# USBStereoAudioCodec.net
KiCad netlist of a schematic drawn in Altium Designer
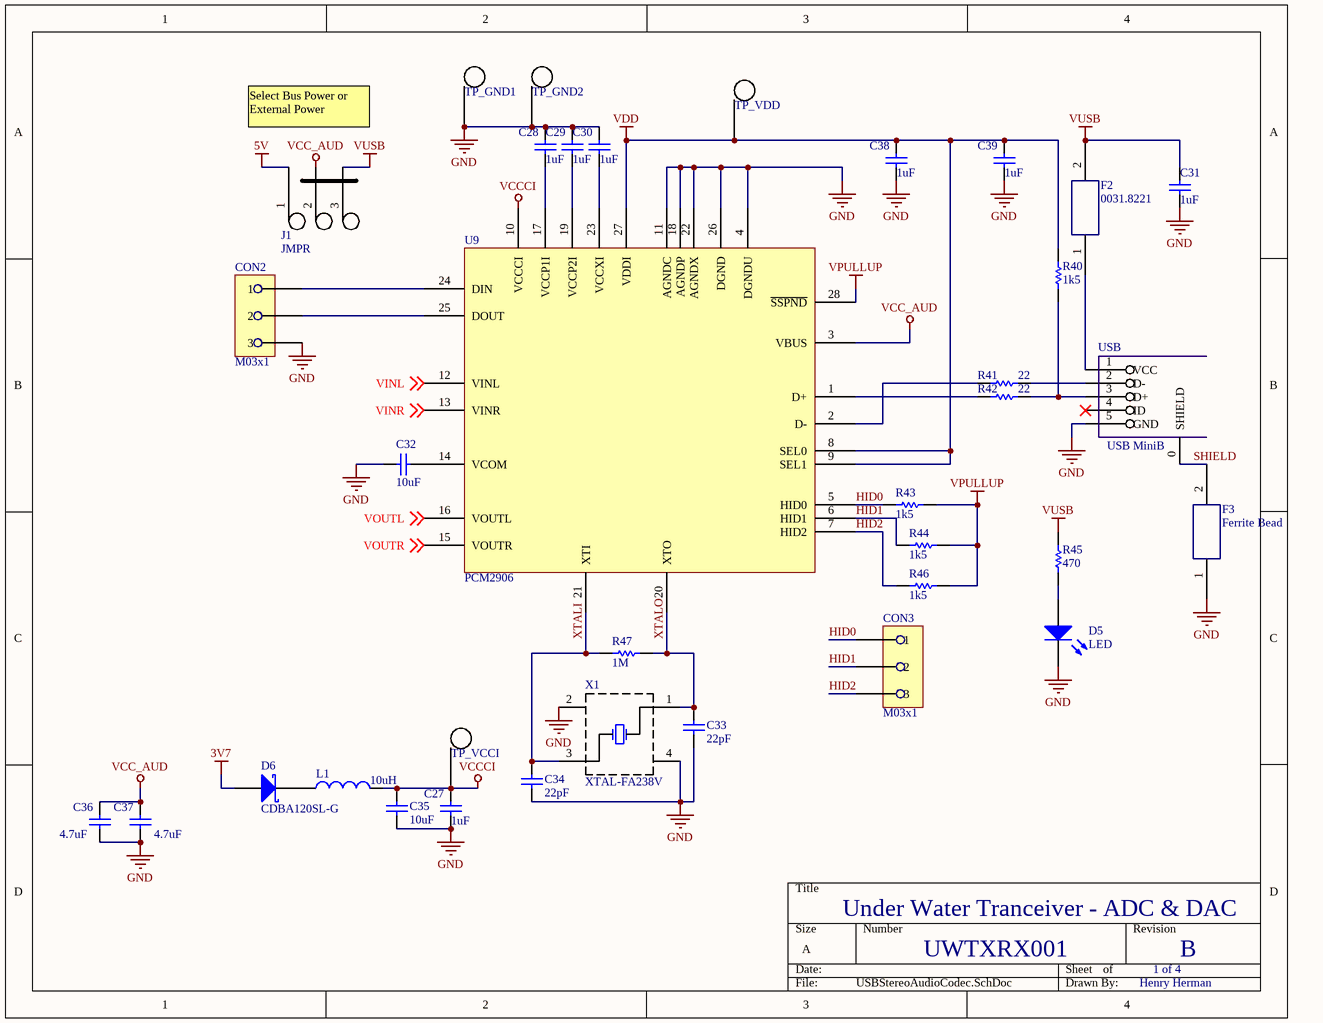
[diagram p0: USBStereoAudioCodec.SchDoc]

(export (version "E")
  (design (tool "Eeschema 10.0.6"))
  (components
    (comp (ref "C27")
      (value "1uF")
      (footprint "SM/C_0805")
      (description "CAP")
      (libsource (lib "Henry1_20_2010") (part "CAP"))
    )
    (comp (ref "C28")
      (value "1uF")
      (footprint "SM/C_0805")
      (description "CAP")
      (libsource (lib "Henry1_20_2010") (part "CAP"))
    )
    (comp (ref "C29")
      (value "1uF")
      (footprint "SM/C_0805")
      (description "CAP")
      (libsource (lib "Henry1_20_2010") (part "CAP"))
    )
    (comp (ref "C30")
      (value "1uF")
      (footprint "SM/C_0805")
      (description "CAP")
      (libsource (lib "Henry1_20_2010") (part "CAP"))
    )
    (comp (ref "C31")
      (value "1uF")
      (footprint "SM/C_0805")
      (description "CAP")
      (libsource (lib "Henry1_20_2010") (part "CAP"))
    )
    (comp (ref "C32")
      (value "10uF")
      (footprint "SM/C_0805")
      (description "CAP")
      (libsource (lib "Henry1_20_2010") (part "CAP"))
    )
    (comp (ref "C33")
      (value "22pF")
      (footprint "SM/C_0805")
      (description "CAP")
      (libsource (lib "Henry1_20_2010") (part "CAP"))
    )
    (comp (ref "C34")
      (value "22pF")
      (footprint "SM/C_0805")
      (description "CAP")
      (libsource (lib "Henry1_20_2010") (part "CAP"))
    )
    (comp (ref "C35")
      (value "10uF")
      (footprint "SM/C_0805")
      (description "CAP")
      (libsource (lib "Henry1_20_2010") (part "CAP"))
    )
    (comp (ref "C36")
      (value "4.7uF")
      (footprint "SM/C_0805")
      (description "CAP")
      (libsource (lib "Henry1_20_2010") (part "CAP"))
    )
    (comp (ref "C37")
      (value "CAP")
      (footprint "SM/C_0805")
      (fields (field (name "LABEL") "4.7uF"))
      (libsource (lib "Henry1_20_2010") (part "CAP"))
    )
    (comp (ref "C38")
      (value "1uF")
      (footprint "SM/C_0805")
      (description "CAP")
      (libsource (lib "Henry1_20_2010") (part "CAP"))
    )
    (comp (ref "C39")
      (value "1uF")
      (footprint "SM/C_0805")
      (description "CAP")
      (libsource (lib "Henry1_20_2010") (part "CAP"))
    )
    (comp (ref "CON2") (value "M03x1") (footprint "M03x1") (libsource (lib "Henry1_20_2010") (part "M03x1")))
    (comp (ref "CON3") (value "M03x1") (footprint "M03x1") (libsource (lib "") (part "M03x1_1")))
    (comp (ref "D5") (value "LED") (footprint "LED-0805") (libsource (lib "Henry1_20_2010") (part "LED")))
    (comp (ref "D6")
      (value "CDBA120SL-G")
      (footprint "D0-214AC")
      (libsource (lib "Henry1_20_2010") (part "Schottky Diode_AC"))
    )
    (comp (ref "F2")
      (value "0031.8221")
      (footprint "SM/R_0805")
      (description "Ferrite Bead")
      (fields (field (name "PUBLISHER") "Altium Limited"))
      (libsource (lib "Henry1_20_2010") (part "Ferrite Bead"))
    )
    (comp (ref "F3")
      (value "Ferrite Bead")
      (footprint "SM/R_0805")
      (fields (field (name "PUBLISHER") "Altium Limited"))
      (libsource (lib "Henry1_20_2010") (part "Ferrite Bead"))
    )
    (comp (ref "J1")
      (value "JMPR")
      (footprint "M03x1-nolock")
      (description "Jumper")
      (fields (field (name "PUBLISHER") "Altium Limited"))
      (libsource (lib "Henry1_20_2010") (part "JMPR-3"))
    )
    (comp (ref "L1")
      (value "10uH")
      (footprint "SM/L_0805")
      (fields (field (name "Comment") "Inductor"))
      (libsource (lib "Henry1_20_2010") (part "Inductor"))
    )
    (comp (ref "R40")
      (value "1k5")
      (footprint "SM/R_0805")
      (description "Resistor")
      (fields (field (name "Comment") "Res") (field (name "PUBLISHER") "Altium Limited"))
      (libsource (lib "Henry1_20_2010") (part "Res"))
    )
    (comp (ref "R41")
      (value "22")
      (footprint "SM/R_0805")
      (description "Resistor")
      (fields (field (name "Comment") "Res") (field (name "PUBLISHER") "Altium Limited"))
      (libsource (lib "Henry1_20_2010") (part "Res"))
    )
    (comp (ref "R42")
      (value "22")
      (footprint "SM/R_0805")
      (description "Resistor")
      (fields (field (name "Comment") "Res") (field (name "PUBLISHER") "Altium Limited"))
      (libsource (lib "Henry1_20_2010") (part "Res"))
    )
    (comp (ref "R43")
      (value "1k5")
      (footprint "SM/R_0805")
      (description "Resistor")
      (fields (field (name "Comment") "Res") (field (name "PUBLISHER") "Altium Limited"))
      (libsource (lib "Henry1_20_2010") (part "Res"))
    )
    (comp (ref "R44")
      (value "1k5")
      (footprint "SM/R_0805")
      (description "Resistor")
      (fields (field (name "Comment") "Res") (field (name "PUBLISHER") "Altium Limited"))
      (libsource (lib "Henry1_20_2010") (part "Res"))
    )
    (comp (ref "R45")
      (value "470")
      (footprint "SM/R_0805")
      (description "Resistor")
      (fields (field (name "Comment") "Res") (field (name "PUBLISHER") "Altium Limited"))
      (libsource (lib "Henry1_20_2010") (part "Res"))
    )
    (comp (ref "R46")
      (value "1k5")
      (footprint "SM/R_0805")
      (description "Resistor")
      (fields (field (name "Comment") "Res") (field (name "PUBLISHER") "Altium Limited"))
      (libsource (lib "Henry1_20_2010") (part "Res"))
    )
    (comp (ref "R47")
      (value "1M")
      (footprint "SM/R_0805")
      (description "Resistor")
      (fields (field (name "Comment") "Res") (field (name "PUBLISHER") "Altium Limited"))
      (libsource (lib "Henry1_20_2010") (part "Res"))
    )
    (comp (ref "TP_GND1")
      (value "TEST_PT")
      (footprint "TEST_PT_SMD")
      (libsource (lib "Henry1_20_2010") (part "TEST_PT"))
    )
    (comp (ref "TP_GND2")
      (value "TEST_PT")
      (footprint "TEST_PT_SMD")
      (libsource (lib "Henry1_20_2010") (part "TEST_PT"))
    )
    (comp (ref "TP_VCCI")
      (value "TEST_PT")
      (footprint "TEST_PT_SMD")
      (libsource (lib "Henry1_20_2010") (part "TEST_PT"))
    )
    (comp (ref "TP_VDD")
      (value "TEST_PT")
      (footprint "TEST_PT_SMD")
      (libsource (lib "Henry1_20_2010") (part "TEST_PT"))
    )
    (comp (ref "U9")
      (value "PCM2906")
      (footprint "SSOP-28PIN-TI")
      (libsource (lib "Henry1_20_2010") (part "PCM2906C"))
    )
    (comp (ref "USB")
      (value "USB MiniB")
      (footprint "USB-MINIB")
      (description "Mini USB")
      (fields (field (name "PUBLISHER") "Altium Limited"))
      (libsource (lib "Henry1_20_2010") (part "USB MiniB"))
    )
    (comp (ref "X1")
      (value "XTAL-FA238V")
      (footprint "XTAL 12MHz SMD")
      (libsource (lib "Henry1_20_2010") (part "XTAL-FA238V"))
    )
  )
  (nets
    (net (code "1") (name "/HID0") (class "Default")
      (node (ref "CON3") (pin "1") (pinfunction "1_1") (pintype "passive"))
      (node (ref "R43") (pin "1") (pinfunction "1_1") (pintype "passive"))
      (node (ref "U9") (pin "5") (pinfunction "HID0_5") (pintype "passive"))
    )
    (net (code "2") (name "/HID1") (class "Default")
      (node (ref "CON3") (pin "2") (pinfunction "2_2") (pintype "passive"))
      (node (ref "R44") (pin "1") (pinfunction "1_1") (pintype "passive"))
      (node (ref "U9") (pin "6") (pinfunction "HID1_6") (pintype "passive"))
    )
    (net (code "3") (name "/HID2") (class "Default")
      (node (ref "CON3") (pin "3") (pinfunction "3_3") (pintype "passive"))
      (node (ref "R46") (pin "1") (pinfunction "1_1") (pintype "passive"))
      (node (ref "U9") (pin "7") (pinfunction "HID2_7") (pintype "passive"))
    )
    (net (code "4") (name "/SHIELD") (class "Default")
      (node (ref "F3") (pin "2") (pintype "power_in"))
      (node (ref "USB") (pin "0") (pinfunction "SHIELD_0") (pintype "power_in"))
    )
    (net (code "5") (name "/XTALI") (class "Default")
      (node (ref "C34") (pin "2") (pinfunction "2_2") (pintype "passive"))
      (node (ref "R47") (pin "2") (pinfunction "2_2") (pintype "passive"))
      (node (ref "U9") (pin "21") (pinfunction "XTI_21") (pintype "passive"))
      (node (ref "X1") (pin "3") (pinfunction "3_3") (pintype "passive"))
    )
    (net (code "6") (name "/XTALO") (class "Default")
      (node (ref "C33") (pin "2") (pinfunction "2_2") (pintype "passive"))
      (node (ref "R47") (pin "1") (pinfunction "1_1") (pintype "passive"))
      (node (ref "U9") (pin "20") (pinfunction "XTO_20") (pintype "passive"))
      (node (ref "X1") (pin "1") (pinfunction "1_1") (pintype "passive"))
    )
    (net (code "7") (name "3V7") (class "Default")
      (node (ref "D6") (pin "A") (pinfunction "A_A") (pintype "passive"))
    )
    (net (code "8") (name "5V") (class "Default")
      (node (ref "J1") (pin "1") (pinfunction "P1_1") (pintype "power_in"))
    )
    (net (code "9") (name "GND") (class "Default")
      (node (ref "C27") (pin "2") (pinfunction "2_2") (pintype "passive"))
      (node (ref "C28") (pin "1") (pinfunction "1_1") (pintype "passive"))
      (node (ref "C29") (pin "1") (pinfunction "1_1") (pintype "passive"))
      (node (ref "C30") (pin "1") (pinfunction "1_1") (pintype "passive"))
      (node (ref "C31") (pin "2") (pinfunction "2_2") (pintype "passive"))
      (node (ref "C32") (pin "2") (pinfunction "2_2") (pintype "passive"))
      (node (ref "C33") (pin "1") (pinfunction "1_1") (pintype "passive"))
      (node (ref "C34") (pin "1") (pinfunction "1_1") (pintype "passive"))
      (node (ref "C35") (pin "1") (pinfunction "1_1") (pintype "passive"))
      (node (ref "C36") (pin "2") (pinfunction "2_2") (pintype "passive"))
      (node (ref "C37") (pin "2") (pinfunction "2_2") (pintype "passive"))
      (node (ref "C38") (pin "2") (pinfunction "2_2") (pintype "passive"))
      (node (ref "C39") (pin "2") (pinfunction "2_2") (pintype "passive"))
      (node (ref "CON2") (pin "3") (pinfunction "3_3") (pintype "passive"))
      (node (ref "D5") (pin "2") (pinfunction "K_2") (pintype "passive"))
      (node (ref "F3") (pin "1") (pintype "power_in"))
      (node (ref "TP_GND1") (pin "1") (pinfunction "TP?_1") (pintype "passive"))
      (node (ref "TP_GND2") (pin "1") (pinfunction "TP?_1") (pintype "passive"))
      (node (ref "U9") (pin "11") (pinfunction "AGNDC_11") (pintype "passive"))
      (node (ref "U9") (pin "18") (pinfunction "AGNDP_18") (pintype "passive"))
      (node (ref "U9") (pin "22") (pinfunction "AGNDX_22") (pintype "passive"))
      (node (ref "U9") (pin "26") (pinfunction "DGND_26") (pintype "passive"))
      (node (ref "U9") (pin "4") (pinfunction "DGNDU_4") (pintype "passive"))
      (node (ref "USB") (pin "5") (pinfunction "GND_5") (pintype "power_in"))
      (node (ref "X1") (pin "2") (pinfunction "2_2") (pintype "passive"))
      (node (ref "X1") (pin "4") (pinfunction "4_4") (pintype "passive"))
    )
    (net (code "10") (name "Net-(D5-A)") (class "Default")
      (node (ref "D5") (pin "1") (pinfunction "A_1") (pintype "passive"))
      (node (ref "R45") (pin "2") (pinfunction "2_2") (pintype "passive"))
    )
    (net (code "11") (name "Net-(D6-PadC)") (class "Default")
      (node (ref "D6") (pin "C") (pinfunction "C_C") (pintype "passive"))
      (node (ref "L1") (pin "1") (pinfunction "1_1") (pintype "passive"))
    )
    (net (code "12") (name "Net-(U9-D+)") (class "Default")
      (node (ref "R42") (pin "1") (pinfunction "1_1") (pintype "passive"))
      (node (ref "U9") (pin "1") (pinfunction "D+_1") (pintype "passive"))
    )
    (net (code "13") (name "Net-(U9-D-)") (class "Default")
      (node (ref "R41") (pin "1") (pinfunction "1_1") (pintype "passive"))
      (node (ref "U9") (pin "2") (pinfunction "D-_2") (pintype "passive"))
    )
    (net (code "14") (name "Net-(U9-DIN)") (class "Default")
      (node (ref "CON2") (pin "1") (pinfunction "1_1") (pintype "passive"))
      (node (ref "U9") (pin "24") (pinfunction "DIN_24") (pintype "passive"))
    )
    (net (code "15") (name "Net-(U9-DOUT)") (class "Default")
      (node (ref "CON2") (pin "2") (pinfunction "2_2") (pintype "passive"))
      (node (ref "U9") (pin "25") (pinfunction "DOUT_25") (pintype "passive"))
    )
    (net (code "16") (name "Net-(U9-VCCP1I)") (class "Default")
      (node (ref "C28") (pin "2") (pinfunction "2_2") (pintype "passive"))
      (node (ref "U9") (pin "17") (pinfunction "VCCP1I_17") (pintype "passive"))
    )
    (net (code "17") (name "Net-(U9-VCCP2I)") (class "Default")
      (node (ref "C29") (pin "2") (pinfunction "2_2") (pintype "passive"))
      (node (ref "U9") (pin "19") (pinfunction "VCCP2I_19") (pintype "passive"))
    )
    (net (code "18") (name "Net-(U9-VCCXI)") (class "Default")
      (node (ref "C30") (pin "2") (pinfunction "2_2") (pintype "passive"))
      (node (ref "U9") (pin "23") (pinfunction "VCCXI_23") (pintype "passive"))
    )
    (net (code "19") (name "Net-(U9-VCOM)") (class "Default")
      (node (ref "C32") (pin "1") (pinfunction "1_1") (pintype "passive"))
      (node (ref "U9") (pin "14") (pinfunction "VCOM_14") (pintype "passive"))
    )
    (net (code "20") (name "Net-(USB-D+)") (class "Default")
      (node (ref "R40") (pin "2") (pinfunction "2_2") (pintype "passive"))
      (node (ref "R42") (pin "2") (pinfunction "2_2") (pintype "passive"))
      (node (ref "USB") (pin "3") (pinfunction "D+_3") (pintype "power_in"))
    )
    (net (code "21") (name "Net-(USB-D-)") (class "Default")
      (node (ref "R41") (pin "2") (pinfunction "2_2") (pintype "passive"))
      (node (ref "USB") (pin "2") (pinfunction "D-_2") (pintype "power_in"))
    )
    (net (code "22") (name "Net-(USB-VCC)") (class "Default")
      (node (ref "F2") (pin "1") (pintype "power_in"))
      (node (ref "USB") (pin "1") (pinfunction "VCC_1") (pintype "power_in"))
    )
    (net (code "23") (name "VCCCI") (class "Default")
      (node (ref "C27") (pin "1") (pinfunction "1_1") (pintype "passive"))
      (node (ref "C35") (pin "2") (pinfunction "2_2") (pintype "passive"))
      (node (ref "L1") (pin "2") (pinfunction "2_2") (pintype "passive"))
      (node (ref "TP_VCCI") (pin "1") (pinfunction "TP?_1") (pintype "passive"))
      (node (ref "U9") (pin "10") (pinfunction "VCCCI_10") (pintype "passive"))
    )
    (net (code "24") (name "VCC_AUD") (class "Default")
      (node (ref "C36") (pin "1") (pinfunction "1_1") (pintype "passive"))
      (node (ref "C37") (pin "1") (pinfunction "1_1") (pintype "passive"))
      (node (ref "J1") (pin "2") (pinfunction "P2_2") (pintype "power_in"))
      (node (ref "U9") (pin "3") (pinfunction "VBUS_3") (pintype "passive"))
    )
    (net (code "25") (name "VDD") (class "Default")
      (node (ref "C38") (pin "1") (pinfunction "1_1") (pintype "passive"))
      (node (ref "C39") (pin "1") (pinfunction "1_1") (pintype "passive"))
      (node (ref "R40") (pin "1") (pinfunction "1_1") (pintype "passive"))
      (node (ref "TP_VDD") (pin "1") (pinfunction "TP?_1") (pintype "passive"))
      (node (ref "U9") (pin "27") (pinfunction "VDDI_27") (pintype "passive"))
      (node (ref "U9") (pin "8") (pinfunction "SEL0_8") (pintype "passive"))
      (node (ref "U9") (pin "9") (pinfunction "SEL1_9") (pintype "passive"))
    )
    (net (code "26") (name "VINL") (class "Default")
      (node (ref "U9") (pin "12") (pinfunction "VINL_12") (pintype "passive"))
    )
    (net (code "27") (name "VINR") (class "Default")
      (node (ref "U9") (pin "13") (pinfunction "VINR_13") (pintype "passive"))
    )
    (net (code "28") (name "VOUTL") (class "Default")
      (node (ref "U9") (pin "16") (pinfunction "VOUTL_16") (pintype "passive"))
    )
    (net (code "29") (name "VOUTR") (class "Default")
      (node (ref "U9") (pin "15") (pinfunction "VOUTR_15") (pintype "passive"))
    )
    (net (code "30") (name "VPULLUP") (class "Default")
      (node (ref "R43") (pin "2") (pinfunction "2_2") (pintype "passive"))
      (node (ref "R44") (pin "2") (pinfunction "2_2") (pintype "passive"))
      (node (ref "R46") (pin "2") (pinfunction "2_2") (pintype "passive"))
      (node (ref "U9") (pin "28") (pinfunction "~{SSPND}_28") (pintype "passive"))
    )
    (net (code "31") (name "VUSB") (class "Default")
      (node (ref "C31") (pin "1") (pinfunction "1_1") (pintype "passive"))
      (node (ref "F2") (pin "2") (pintype "power_in"))
      (node (ref "J1") (pin "3") (pinfunction "3_3") (pintype "power_in"))
      (node (ref "R45") (pin "1") (pinfunction "1_1") (pintype "passive"))
    )
    (net (code "32") (name "unconnected-(USB-ID-Pad4)") (class "Default")
      (node (ref "USB") (pin "4") (pinfunction "ID_4") (pintype "power_in+no_connect"))
    )
  )
)
